# Nand8Bit.net
KiCad netlist of a schematic drawn in Altium Designer
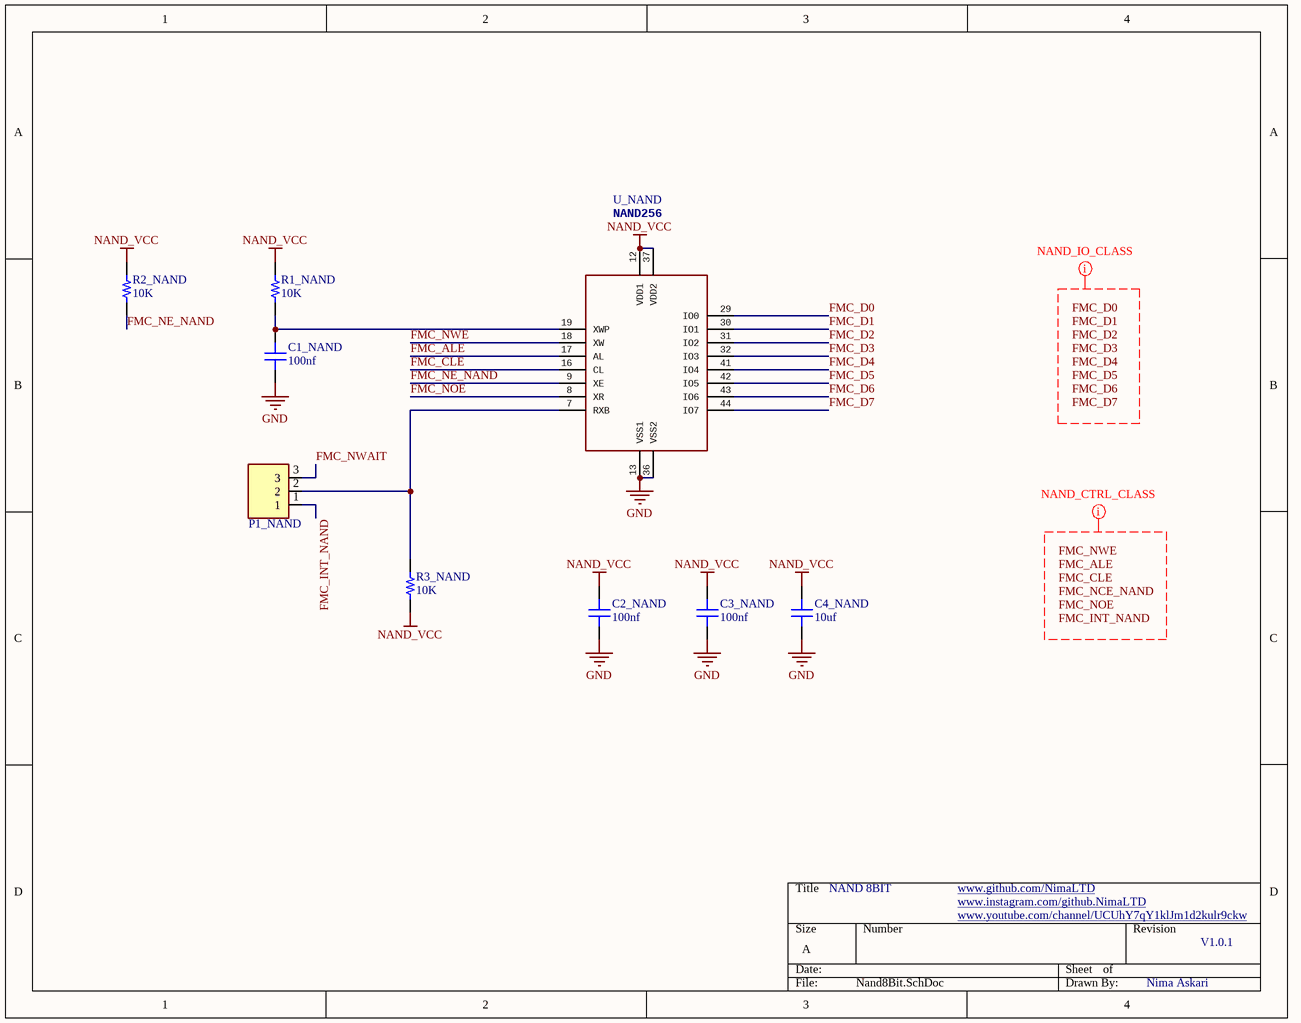
[diagram p0: Nand8Bit.SchDoc]

(export (version "E")
  (design (tool "Eeschema 10.0.6"))
  (components
    (comp (ref "C1_NAND")
      (value "100nf")
      (footprint "CAP 0805")
      (description "SMT Capacitor")
      (libsource (lib "CAPACITOR") (part "Cap SMD 0805"))
    )
    (comp (ref "C2_NAND")
      (value "100nf")
      (footprint "CAP 0805")
      (description "SMT Capacitor")
      (libsource (lib "CAPACITOR") (part "Cap SMD 0805"))
    )
    (comp (ref "C3_NAND")
      (value "100nf")
      (footprint "CAP 0805")
      (description "SMT Capacitor")
      (libsource (lib "CAPACITOR") (part "Cap SMD 0805"))
    )
    (comp (ref "C4_NAND")
      (value "10uf")
      (footprint "CAP 0805")
      (description "SMT Capacitor")
      (libsource (lib "CAPACITOR") (part "Cap SMD 0805"))
    )
    (comp (ref "P1_NAND")
      (value "CONN_PWL_3")
      (footprint "SOLDER 3Pin SELECTOR")
      (libsource (lib "CONNECTOR") (part "Solder 3Pin Selector"))
    )
    (comp (ref "R1_NAND")
      (value "10K")
      (footprint "RES 0805")
      (description "SMD Resistor")
      (libsource (lib "RESISTOR") (part "Res SMD 0805"))
    )
    (comp (ref "R2_NAND")
      (value "10K")
      (footprint "RES 0805")
      (description "SMD Resistor")
      (libsource (lib "RESISTOR") (part "Res SMD 0805"))
    )
    (comp (ref "R3_NAND")
      (value "10K")
      (footprint "RES 0805")
      (description "SMD Resistor")
      (libsource (lib "RESISTOR") (part "Res SMD 0805"))
    )
    (comp (ref "U_NAND") (value "NAND256") (footprint "TSOP48") (libsource (lib "IC") (part "NAND256")))
  )
  (nets
    (net (code "1") (name "/FMC_ALE") (class "Default")
      (node (ref "U_NAND") (pin "17") (pinfunction "AL_17") (pintype "passive"))
    )
    (net (code "2") (name "/FMC_CLE") (class "Default")
      (node (ref "U_NAND") (pin "16") (pinfunction "CL_16") (pintype "passive"))
    )
    (net (code "3") (name "/FMC_D0") (class "Default")
      (node (ref "U_NAND") (pin "29") (pinfunction "IO0_29") (pintype "passive"))
    )
    (net (code "4") (name "/FMC_D1") (class "Default")
      (node (ref "U_NAND") (pin "30") (pinfunction "IO1_30") (pintype "passive"))
    )
    (net (code "5") (name "/FMC_D2") (class "Default")
      (node (ref "U_NAND") (pin "31") (pinfunction "IO2_31") (pintype "passive"))
    )
    (net (code "6") (name "/FMC_D3") (class "Default")
      (node (ref "U_NAND") (pin "32") (pinfunction "IO3_32") (pintype "passive"))
    )
    (net (code "7") (name "/FMC_D4") (class "Default")
      (node (ref "U_NAND") (pin "41") (pinfunction "IO4_41") (pintype "passive"))
    )
    (net (code "8") (name "/FMC_D5") (class "Default")
      (node (ref "U_NAND") (pin "42") (pinfunction "IO5_42") (pintype "passive"))
    )
    (net (code "9") (name "/FMC_D6") (class "Default")
      (node (ref "U_NAND") (pin "43") (pinfunction "IO6_43") (pintype "passive"))
    )
    (net (code "10") (name "/FMC_D7") (class "Default")
      (node (ref "U_NAND") (pin "44") (pinfunction "IO7_44") (pintype "passive"))
    )
    (net (code "11") (name "/FMC_INT_NAND") (class "Default")
      (node (ref "P1_NAND") (pin "1") (pinfunction "1_1") (pintype "passive"))
    )
    (net (code "13") (name "/FMC_NE_NAND") (class "Default")
      (node (ref "R2_NAND") (pin "1") (pinfunction "1_1") (pintype "passive"))
      (node (ref "U_NAND") (pin "9") (pinfunction "XE_9") (pintype "passive"))
    )
    (net (code "14") (name "/FMC_NOE") (class "Default")
      (node (ref "U_NAND") (pin "8") (pinfunction "XR_8") (pintype "passive"))
    )
    (net (code "15") (name "/FMC_NWAIT") (class "Default")
      (node (ref "P1_NAND") (pin "3") (pinfunction "3_3") (pintype "passive"))
    )
    (net (code "16") (name "/FMC_NWE") (class "Default")
      (node (ref "U_NAND") (pin "18") (pinfunction "XW_18") (pintype "passive"))
    )
    (net (code "17") (name "GND") (class "Default")
      (node (ref "C1_NAND") (pin "1") (pinfunction "1_1") (pintype "passive"))
      (node (ref "C2_NAND") (pin "1") (pinfunction "1_1") (pintype "passive"))
      (node (ref "C3_NAND") (pin "1") (pinfunction "1_1") (pintype "passive"))
      (node (ref "C4_NAND") (pin "1") (pinfunction "1_1") (pintype "passive"))
      (node (ref "U_NAND") (pin "13") (pinfunction "VSS1_13") (pintype "passive"))
      (node (ref "U_NAND") (pin "36") (pinfunction "VSS2_36") (pintype "passive"))
    )
    (net (code "18") (name "NAND_VCC") (class "Default")
      (node (ref "C2_NAND") (pin "2") (pinfunction "2_2") (pintype "passive"))
      (node (ref "C3_NAND") (pin "2") (pinfunction "2_2") (pintype "passive"))
      (node (ref "C4_NAND") (pin "2") (pinfunction "2_2") (pintype "passive"))
      (node (ref "R1_NAND") (pin "2") (pinfunction "2_2") (pintype "passive"))
      (node (ref "R2_NAND") (pin "2") (pinfunction "2_2") (pintype "passive"))
      (node (ref "R3_NAND") (pin "2") (pinfunction "2_2") (pintype "passive"))
      (node (ref "U_NAND") (pin "12") (pinfunction "VDD1_12") (pintype "passive"))
      (node (ref "U_NAND") (pin "37") (pinfunction "VDD2_37") (pintype "passive"))
    )
    (net (code "19") (name "Net-(U_NAND-RXB)") (class "Default")
      (node (ref "P1_NAND") (pin "2") (pinfunction "2_2") (pintype "passive"))
      (node (ref "R3_NAND") (pin "1") (pinfunction "1_1") (pintype "passive"))
      (node (ref "U_NAND") (pin "7") (pinfunction "RXB_7") (pintype "passive"))
    )
    (net (code "20") (name "Net-(U_NAND-XWP)") (class "Default")
      (node (ref "C1_NAND") (pin "2") (pinfunction "2_2") (pintype "passive"))
      (node (ref "R1_NAND") (pin "1") (pinfunction "1_1") (pintype "passive"))
      (node (ref "U_NAND") (pin "19") (pinfunction "XWP_19") (pintype "passive"))
    )
  )
)
